# OSD-board.net
KiCad netlist of a schematic drawn in EAGLE
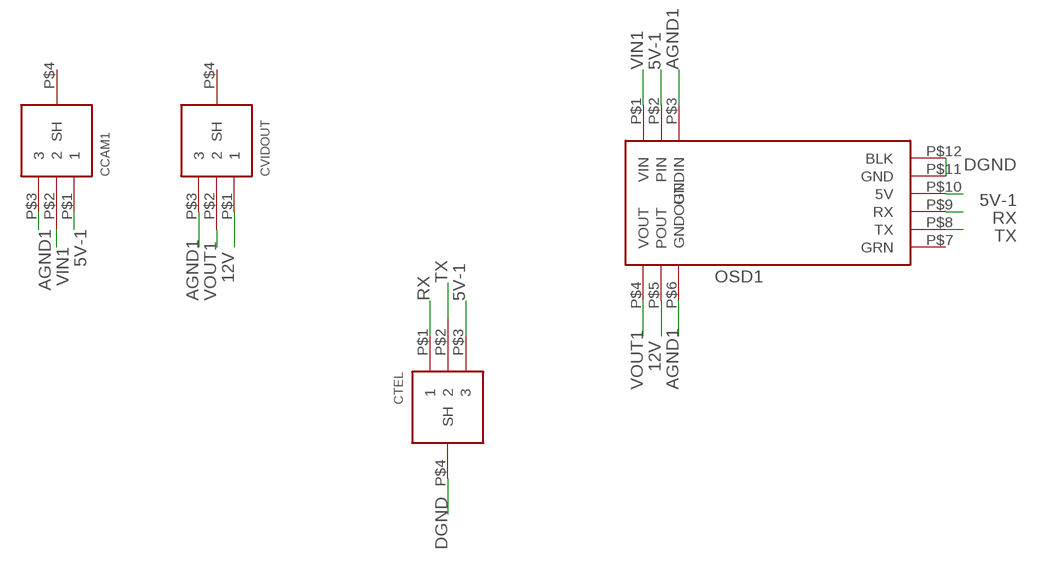
[diagram p0: schematic, sheet 1]

(export (version "E")
  (design (tool "Eeschema 10.0.6"))
  (components
    (comp (ref "CCAM1")
      (value "TRA3M")
      (footprint "eagle-import:TRA3M")
      (libsource (lib "eagle-import") (part "TRA3M"))
    )
    (comp (ref "CTEL")
      (value "TRA3MBARE")
      (footprint "eagle-import:TRA3M-BARE")
      (libsource (lib "eagle-import") (part "TRA3MBARE"))
    )
    (comp (ref "CVIDOUT")
      (value "TRA3M")
      (footprint "eagle-import:TRA3M")
      (libsource (lib "eagle-import") (part "TRA3M"))
    )
    (comp (ref "OSD1")
      (value "MINIM-OSD")
      (footprint "eagle-import:MINIM-OSD")
      (libsource (lib "eagle-import") (part "MINIM-OSD"))
    )
  )
  (nets
    (net (code "1") (name "/5V-1") (class "Default")
      (node (ref "CCAM1") (pin "P$1") (pinfunction "1_P$1") (pintype "bidirectional"))
      (node (ref "CTEL") (pin "P$3") (pinfunction "3_P$3") (pintype "bidirectional"))
      (node (ref "OSD1") (pin "P$10") (pinfunction "5V_P$10") (pintype "bidirectional"))
      (node (ref "OSD1") (pin "P$2") (pinfunction "PIN_P$2") (pintype "bidirectional"))
    )
    (net (code "2") (name "/12V") (class "Default")
      (node (ref "CVIDOUT") (pin "P$1") (pinfunction "1_P$1") (pintype "bidirectional"))
      (node (ref "OSD1") (pin "P$5") (pinfunction "POUT_P$5") (pintype "bidirectional"))
    )
    (net (code "3") (name "/AGND1") (class "Default")
      (node (ref "CCAM1") (pin "P$3") (pinfunction "3_P$3") (pintype "bidirectional"))
      (node (ref "CVIDOUT") (pin "P$3") (pinfunction "3_P$3") (pintype "bidirectional"))
      (node (ref "OSD1") (pin "P$3") (pinfunction "GNDIN_P$3") (pintype "bidirectional"))
      (node (ref "OSD1") (pin "P$6") (pinfunction "GNDOUT_P$6") (pintype "bidirectional"))
    )
    (net (code "4") (name "/DGND") (class "Default")
      (node (ref "CTEL") (pin "P$4") (pinfunction "SH_P$4") (pintype "bidirectional"))
      (node (ref "OSD1") (pin "P$11") (pinfunction "GND_P$11") (pintype "bidirectional"))
      (node (ref "OSD1") (pin "P$12") (pinfunction "BLK_P$12") (pintype "bidirectional"))
    )
    (net (code "5") (name "/RX") (class "Default")
      (node (ref "CTEL") (pin "P$1") (pinfunction "1_P$1") (pintype "bidirectional"))
      (node (ref "OSD1") (pin "P$9") (pinfunction "RX_P$9") (pintype "bidirectional"))
    )
    (net (code "6") (name "/TX") (class "Default")
      (node (ref "CTEL") (pin "P$2") (pinfunction "2_P$2") (pintype "bidirectional"))
      (node (ref "OSD1") (pin "P$8") (pinfunction "TX_P$8") (pintype "bidirectional"))
    )
    (net (code "7") (name "/VIN1") (class "Default")
      (node (ref "CCAM1") (pin "P$2") (pinfunction "2_P$2") (pintype "bidirectional"))
      (node (ref "OSD1") (pin "P$1") (pinfunction "VIN_P$1") (pintype "bidirectional"))
    )
    (net (code "8") (name "/VOUT1") (class "Default")
      (node (ref "CVIDOUT") (pin "P$2") (pinfunction "2_P$2") (pintype "bidirectional"))
      (node (ref "OSD1") (pin "P$4") (pinfunction "VOUT_P$4") (pintype "bidirectional"))
    )
    (net (code "9") (name "unconnected-(CCAM1-SH-PadP$4)") (class "Default")
      (node (ref "CCAM1") (pin "P$4") (pinfunction "SH_P$4") (pintype "bidirectional"))
    )
    (net (code "10") (name "unconnected-(CVIDOUT-SH-PadP$4)") (class "Default")
      (node (ref "CVIDOUT") (pin "P$4") (pinfunction "SH_P$4") (pintype "bidirectional"))
    )
    (net (code "11") (name "unconnected-(OSD1-GRN-PadP$7)") (class "Default")
      (node (ref "OSD1") (pin "P$7") (pinfunction "GRN_P$7") (pintype "bidirectional"))
    )
  )
)
